# 9VPart.net
KiCad netlist of a schematic drawn in EAGLE
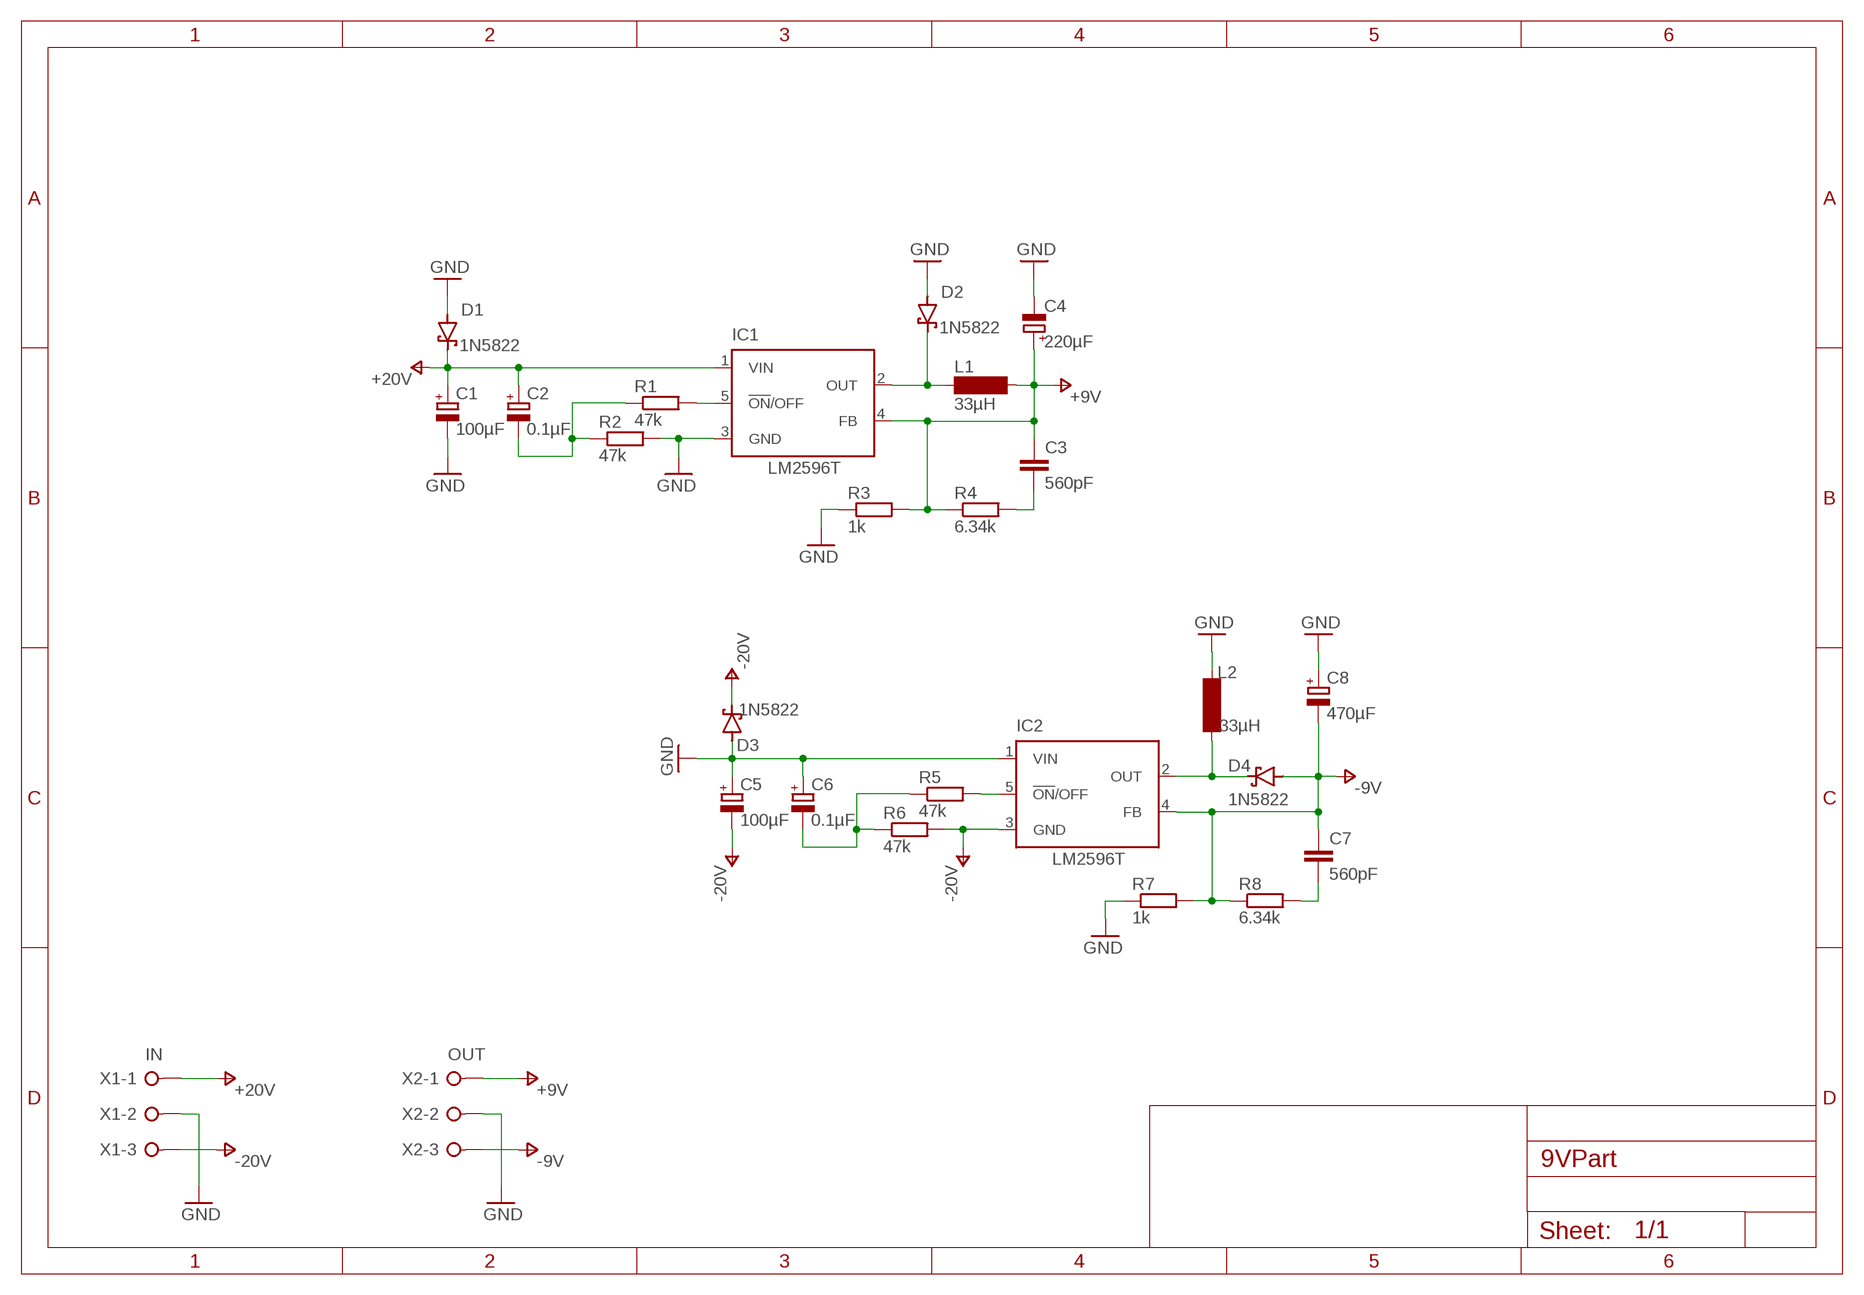
[diagram p0: schematic, sheet 1]

(export (version "E")
  (design (tool "Eeschema 10.0.6"))
  (components
    (comp (ref "C1")
      (value "100µF")
      (footprint "eagle-import:E2,5-6")
      (libsource (lib "eagle-import") (part "CPOL-EUE2.5-6"))
    )
    (comp (ref "C2")
      (value "0.1µF")
      (footprint "eagle-import:E1,8-4")
      (libsource (lib "eagle-import") (part "CPOL-EUE1.8-4"))
    )
    (comp (ref "C3")
      (value "560pF")
      (footprint "eagle-import:C050-024X044")
      (libsource (lib "eagle-import") (part "C-EU050-024X044"))
    )
    (comp (ref "C4")
      (value "220µF")
      (footprint "eagle-import:E3,5-8")
      (libsource (lib "eagle-import") (part "CPOL-EUE3.5-8"))
    )
    (comp (ref "C5")
      (value "100µF")
      (footprint "eagle-import:E2,5-6")
      (libsource (lib "eagle-import") (part "CPOL-EUE2.5-6"))
    )
    (comp (ref "C6")
      (value "0.1µF")
      (footprint "eagle-import:E1,8-4")
      (libsource (lib "eagle-import") (part "CPOL-EUE1.8-4"))
    )
    (comp (ref "C7")
      (value "560pF")
      (footprint "eagle-import:C050-024X044")
      (libsource (lib "eagle-import") (part "C-EU050-024X044"))
    )
    (comp (ref "C8")
      (value "470µF")
      (footprint "eagle-import:E3,5-8")
      (libsource (lib "eagle-import") (part "CPOL-EUE3.5-8"))
    )
    (comp (ref "D1")
      (value "1N5822")
      (footprint "eagle-import:C4111-15")
      (libsource (lib "eagle-import") (part "SCHOTTKY-DIODEC4111-15"))
    )
    (comp (ref "D2")
      (value "1N5822")
      (footprint "eagle-import:C4111-15")
      (libsource (lib "eagle-import") (part "SCHOTTKY-DIODEC4111-15"))
    )
    (comp (ref "D3")
      (value "1N5822")
      (footprint "eagle-import:C4111-15")
      (libsource (lib "eagle-import") (part "SCHOTTKY-DIODEC4111-15"))
    )
    (comp (ref "D4")
      (value "1N5822")
      (footprint "eagle-import:C4111-15")
      (libsource (lib "eagle-import") (part "SCHOTTKY-DIODEC4111-15"))
    )
    (comp (ref "IC1")
      (value "LM2596T")
      (footprint "eagle-import:T05D")
      (fields (field (name "MPN") "LM2596T-ADJ/LF02"))
      (libsource (lib "eagle-import") (part "LM2596T"))
    )
    (comp (ref "IC2")
      (value "LM2596T")
      (footprint "eagle-import:T05D")
      (fields (field (name "MPN") "LM2596T-ADJ/LF02"))
      (libsource (lib "eagle-import") (part "LM2596T"))
    )
    (comp (ref "L1")
      (value "33µH")
      (footprint "eagle-import:IND-120")
      (libsource (lib "eagle-import") (part "IND-120-330K"))
    )
    (comp (ref "L2")
      (value "33µH")
      (footprint "eagle-import:IND-120")
      (libsource (lib "eagle-import") (part "IND-120-330K"))
    )
    (comp (ref "R1")
      (value "47k")
      (footprint "eagle-import:0207_10")
      (libsource (lib "eagle-import") (part "R-EU_0207/10"))
    )
    (comp (ref "R2")
      (value "47k")
      (footprint "eagle-import:0207_10")
      (libsource (lib "eagle-import") (part "R-EU_0207/10"))
    )
    (comp (ref "R3")
      (value "1k")
      (footprint "eagle-import:0207_10")
      (libsource (lib "eagle-import") (part "R-EU_0207/10"))
    )
    (comp (ref "R4")
      (value "6.34k")
      (footprint "eagle-import:0207_10")
      (libsource (lib "eagle-import") (part "R-EU_0207/10"))
    )
    (comp (ref "R5")
      (value "47k")
      (footprint "eagle-import:0207_10")
      (libsource (lib "eagle-import") (part "R-EU_0207/10"))
    )
    (comp (ref "R6")
      (value "47k")
      (footprint "eagle-import:0207_10")
      (libsource (lib "eagle-import") (part "R-EU_0207/10"))
    )
    (comp (ref "R7")
      (value "1k")
      (footprint "eagle-import:0207_10")
      (libsource (lib "eagle-import") (part "R-EU_0207/10"))
    )
    (comp (ref "R8")
      (value "6.34k")
      (footprint "eagle-import:0207_10")
      (libsource (lib "eagle-import") (part "R-EU_0207/10"))
    )
    (comp (ref "X1")
      (value "IN")
      (footprint "eagle-import:W237-133")
      (libsource (lib "eagle-import") (part "W237-03P"))
    )
    (comp (ref "X2")
      (value "OUT")
      (footprint "eagle-import:W237-133")
      (libsource (lib "eagle-import") (part "W237-03P"))
    )
  )
  (nets
    (net (code "1") (name "+9V") (class "Default")
      (node (ref "C3") (pin "1") (pinfunction "1_1") (pintype "passive"))
      (node (ref "C4") (pin "+") (pinfunction "+_+") (pintype "passive"))
      (node (ref "IC1") (pin "4") (pinfunction "FB_4") (pintype "input"))
      (node (ref "L1") (pin "P$2") (pinfunction "2_P$2") (pintype "passive"))
      (node (ref "R3") (pin "2") (pinfunction "2_2") (pintype "passive"))
      (node (ref "R4") (pin "1") (pinfunction "1_1") (pintype "passive"))
      (node (ref "X2") (pin "1") (pinfunction "KL_1") (pintype "passive"))
    )
    (net (code "2") (name "+20V") (class "Default")
      (node (ref "C1") (pin "+") (pinfunction "+_+") (pintype "passive"))
      (node (ref "C2") (pin "+") (pinfunction "+_+") (pintype "passive"))
      (node (ref "D1") (pin "C") (pinfunction "C_C") (pintype "passive"))
      (node (ref "IC1") (pin "1") (pinfunction "VIN_1") (pintype "input"))
      (node (ref "X1") (pin "1") (pinfunction "KL_1") (pintype "passive"))
    )
    (net (code "3") (name "-9V") (class "Default")
      (node (ref "C7") (pin "1") (pinfunction "1_1") (pintype "passive"))
      (node (ref "C8") (pin "-") (pinfunction "-_-") (pintype "passive"))
      (node (ref "D4") (pin "A") (pinfunction "A_A") (pintype "passive"))
      (node (ref "IC2") (pin "4") (pinfunction "FB_4") (pintype "input"))
      (node (ref "R7") (pin "2") (pinfunction "2_2") (pintype "passive"))
      (node (ref "R8") (pin "1") (pinfunction "1_1") (pintype "passive"))
      (node (ref "X2") (pin "3") (pinfunction "KL_3") (pintype "passive"))
    )
    (net (code "4") (name "-20V") (class "Default")
      (node (ref "C5") (pin "-") (pinfunction "-_-") (pintype "passive"))
      (node (ref "D3") (pin "C") (pinfunction "C_C") (pintype "passive"))
      (node (ref "IC2") (pin "3") (pinfunction "GND_3") (pintype "power_in"))
      (node (ref "R6") (pin "2") (pinfunction "2_2") (pintype "passive"))
      (node (ref "X1") (pin "3") (pinfunction "KL_3") (pintype "passive"))
    )
    (net (code "5") (name "GND") (class "Default")
      (node (ref "C1") (pin "-") (pinfunction "-_-") (pintype "passive"))
      (node (ref "C4") (pin "-") (pinfunction "-_-") (pintype "passive"))
      (node (ref "C5") (pin "+") (pinfunction "+_+") (pintype "passive"))
      (node (ref "C6") (pin "+") (pinfunction "+_+") (pintype "passive"))
      (node (ref "C8") (pin "+") (pinfunction "+_+") (pintype "passive"))
      (node (ref "D1") (pin "A") (pinfunction "A_A") (pintype "passive"))
      (node (ref "D2") (pin "A") (pinfunction "A_A") (pintype "passive"))
      (node (ref "D3") (pin "A") (pinfunction "A_A") (pintype "passive"))
      (node (ref "IC1") (pin "3") (pinfunction "GND_3") (pintype "power_in"))
      (node (ref "IC2") (pin "1") (pinfunction "VIN_1") (pintype "input"))
      (node (ref "L2") (pin "P$2") (pinfunction "2_P$2") (pintype "passive"))
      (node (ref "R2") (pin "2") (pinfunction "2_2") (pintype "passive"))
      (node (ref "R3") (pin "1") (pinfunction "1_1") (pintype "passive"))
      (node (ref "R7") (pin "1") (pinfunction "1_1") (pintype "passive"))
      (node (ref "X1") (pin "2") (pinfunction "KL_2") (pintype "passive"))
      (node (ref "X2") (pin "2") (pinfunction "KL_2") (pintype "passive"))
    )
    (net (code "6") (name "Net-(C2-Pad-)") (class "Default")
      (node (ref "C2") (pin "-") (pinfunction "-_-") (pintype "passive"))
      (node (ref "R1") (pin "1") (pinfunction "1_1") (pintype "passive"))
      (node (ref "R2") (pin "1") (pinfunction "1_1") (pintype "passive"))
    )
    (net (code "7") (name "Net-(C3-Pad2)") (class "Default")
      (node (ref "C3") (pin "2") (pinfunction "2_2") (pintype "passive"))
      (node (ref "R4") (pin "2") (pinfunction "2_2") (pintype "passive"))
    )
    (net (code "8") (name "Net-(C6-Pad-)") (class "Default")
      (node (ref "C6") (pin "-") (pinfunction "-_-") (pintype "passive"))
      (node (ref "R5") (pin "1") (pinfunction "1_1") (pintype "passive"))
      (node (ref "R6") (pin "1") (pinfunction "1_1") (pintype "passive"))
    )
    (net (code "9") (name "Net-(C7-Pad2)") (class "Default")
      (node (ref "C7") (pin "2") (pinfunction "2_2") (pintype "passive"))
      (node (ref "R8") (pin "2") (pinfunction "2_2") (pintype "passive"))
    )
    (net (code "10") (name "Net-(IC1-OUT)") (class "Default")
      (node (ref "D2") (pin "C") (pinfunction "C_C") (pintype "passive"))
      (node (ref "IC1") (pin "2") (pinfunction "OUT_2") (pintype "output"))
      (node (ref "L1") (pin "P$1") (pinfunction "1_P$1") (pintype "passive"))
    )
    (net (code "11") (name "Net-(IC1-~{ON}{slash}OFF)") (class "Default")
      (node (ref "IC1") (pin "5") (pinfunction "~{ON}/OFF_5") (pintype "input"))
      (node (ref "R1") (pin "2") (pinfunction "2_2") (pintype "passive"))
    )
    (net (code "12") (name "Net-(IC2-OUT)") (class "Default")
      (node (ref "D4") (pin "C") (pinfunction "C_C") (pintype "passive"))
      (node (ref "IC2") (pin "2") (pinfunction "OUT_2") (pintype "output"))
      (node (ref "L2") (pin "P$1") (pinfunction "1_P$1") (pintype "passive"))
    )
    (net (code "13") (name "Net-(IC2-~{ON}{slash}OFF)") (class "Default")
      (node (ref "IC2") (pin "5") (pinfunction "~{ON}/OFF_5") (pintype "input"))
      (node (ref "R5") (pin "2") (pinfunction "2_2") (pintype "passive"))
    )
  )
)
